# Acc_Comp_Gyro.net
KiCad netlist of a schematic drawn in EAGLE
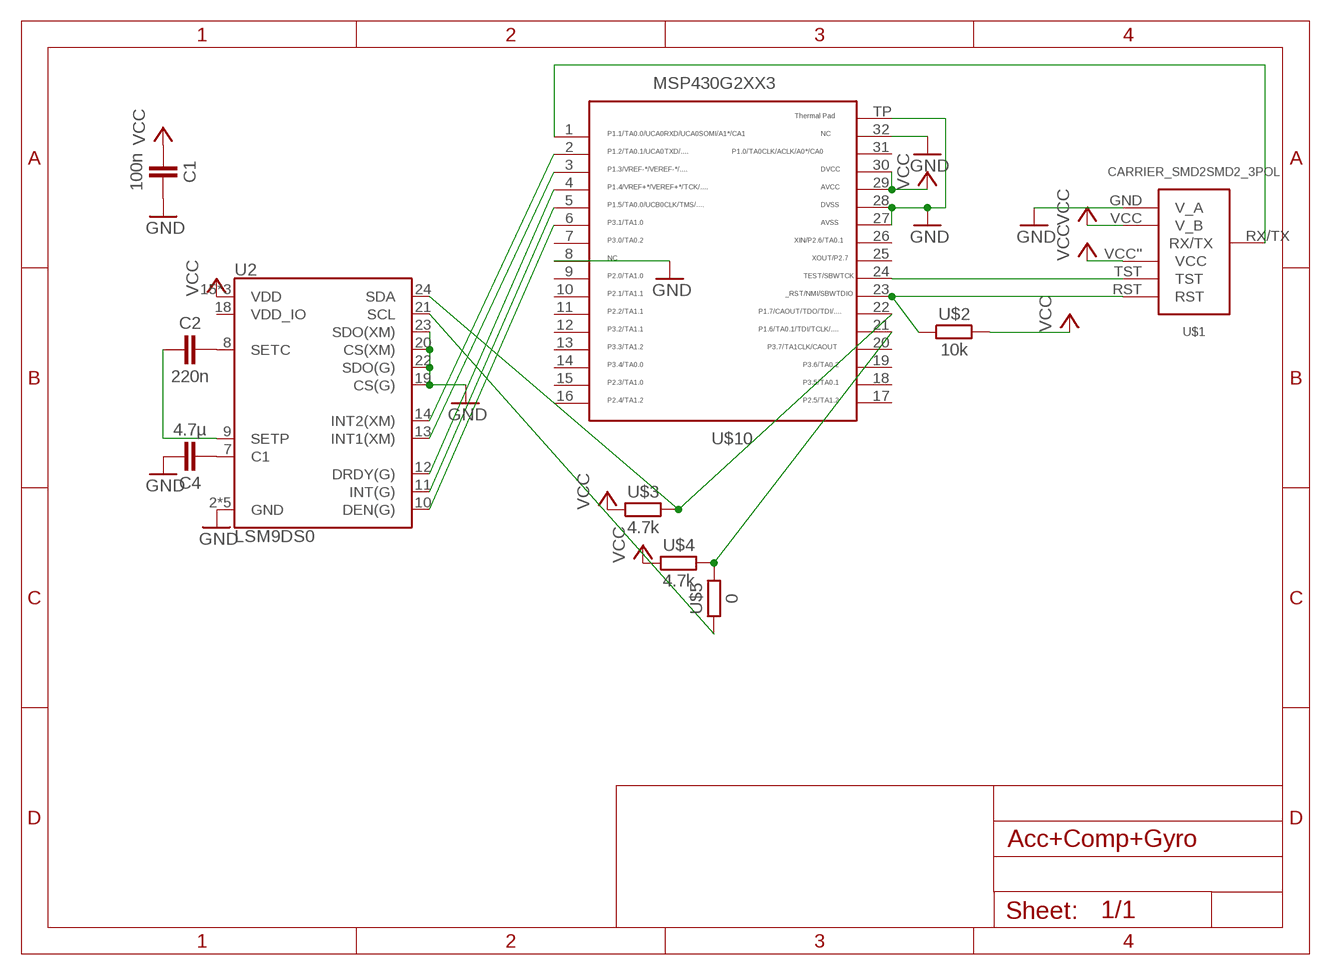
[diagram p0: schematic, sheet 1]

(export (version "E")
  (design (tool "Eeschema 10.0.6"))
  (components
    (comp (ref "C1")
      (value "100n")
      (footprint "eagle-import:603")
      (libsource (lib "eagle-import") (part "CAPACITOR"))
    )
    (comp (ref "C2")
      (value "220n")
      (footprint "eagle-import:603")
      (libsource (lib "eagle-import") (part "CAPACITOR"))
    )
    (comp (ref "C4")
      (value "4.7µ")
      (footprint "eagle-import:603")
      (libsource (lib "eagle-import") (part "CAPACITOR"))
    )
    (comp (ref "U$1")
      (value "CARRIER_SMD2SMD2_3POL")
      (footprint "eagle-import:CARRIER_SMD2_3POL")
      (libsource (lib "eagle-import") (part "CARRIER_SMD2SMD2_3POL"))
    )
    (comp (ref "U$2")
      (value "10k")
      (footprint "eagle-import:603")
      (libsource (lib "eagle-import") (part "RESISTOR0603"))
    )
    (comp (ref "U$3")
      (value "4.7k")
      (footprint "eagle-import:603")
      (libsource (lib "eagle-import") (part "RESISTOR0603"))
    )
    (comp (ref "U$4")
      (value "4.7k")
      (footprint "eagle-import:603")
      (libsource (lib "eagle-import") (part "RESISTOR0603"))
    )
    (comp (ref "U$5")
      (value "0")
      (footprint "eagle-import:603")
      (libsource (lib "eagle-import") (part "RESISTOR0603"))
    )
    (comp (ref "U$10")
      (value "MSP430G2553")
      (footprint "eagle-import:QFN32")
      (libsource (lib "eagle-import") (part "MSP430G2553"))
    )
    (comp (ref "U2")
      (value "LSM9DS0")
      (footprint "eagle-import:LGA-24")
      (libsource (lib "eagle-import") (part "LSM9DS0"))
    )
  )
  (nets
    (net (code "1") (name "GND") (class "Default")
      (node (ref "C1") (pin "2") (pinfunction "2_2") (pintype "passive"))
      (node (ref "C4") (pin "2") (pinfunction "2_2") (pintype "passive"))
      (node (ref "U$1") (pin "GND") (pinfunction "V_A_GND") (pintype "bidirectional"))
      (node (ref "U$10") (pin "27") (pinfunction "27_27") (pintype "bidirectional"))
      (node (ref "U$10") (pin "28") (pinfunction "28_28") (pintype "bidirectional"))
      (node (ref "U$10") (pin "32") (pinfunction "32_32") (pintype "bidirectional"))
      (node (ref "U$10") (pin "8") (pinfunction "8_8") (pintype "bidirectional"))
      (node (ref "U$10") (pin "TP") (pinfunction "TP_TP") (pintype "bidirectional"))
      (node (ref "U2") (pin "19") (pinfunction "CS(G)_19") (pintype "bidirectional"))
      (node (ref "U2") (pin "2") (pinfunction "GND_2") (pintype "bidirectional"))
      (node (ref "U2") (pin "20") (pinfunction "CS(XM)_20") (pintype "bidirectional"))
      (node (ref "U2") (pin "22") (pinfunction "SDO(G)_22") (pintype "bidirectional"))
      (node (ref "U2") (pin "23") (pinfunction "SDO(XM)_23") (pintype "bidirectional"))
      (node (ref "U2") (pin "3") (pinfunction "GND_3") (pintype "bidirectional"))
      (node (ref "U2") (pin "4") (pinfunction "GND_4") (pintype "bidirectional"))
      (node (ref "U2") (pin "5") (pinfunction "GND_5") (pintype "bidirectional"))
      (node (ref "U2") (pin "6") (pinfunction "GND_6") (pintype "bidirectional"))
    )
    (net (code "2") (name "Net-(U$1-PadRST)") (class "Default")
      (node (ref "U$1") (pin "RST") (pinfunction "RST_RST") (pintype "bidirectional"))
      (node (ref "U$10") (pin "23") (pinfunction "23_23") (pintype "bidirectional"))
      (node (ref "U$2") (pin "1") (pinfunction "1_1") (pintype "passive"))
    )
    (net (code "3") (name "Net-(U$1-PadRX{slash}TX)") (class "Default")
      (node (ref "U$1") (pin "RX/TX") (pinfunction "RX/TX_RX/TX") (pintype "bidirectional"))
      (node (ref "U$10") (pin "1") (pinfunction "1_1") (pintype "bidirectional"))
    )
    (net (code "4") (name "Net-(U$1-PadTST)") (class "Default")
      (node (ref "U$1") (pin "TST") (pinfunction "TST_TST") (pintype "bidirectional"))
      (node (ref "U$10") (pin "24") (pinfunction "24_24") (pintype "bidirectional"))
    )
    (net (code "5") (name "Net-(U$10-Pad21)") (class "Default")
      (node (ref "U$10") (pin "21") (pinfunction "21_21") (pintype "bidirectional"))
      (node (ref "U$4") (pin "2") (pinfunction "2_2") (pintype "passive"))
      (node (ref "U$5") (pin "2") (pinfunction "2_2") (pintype "passive"))
    )
    (net (code "6") (name "Net-(U2-C1)") (class "Default")
      (node (ref "C4") (pin "1") (pinfunction "1_1") (pintype "passive"))
      (node (ref "U2") (pin "7") (pinfunction "C1_7") (pintype "bidirectional"))
    )
    (net (code "7") (name "Net-(U2-DEN(G))") (class "Default")
      (node (ref "U$10") (pin "6") (pinfunction "6_6") (pintype "bidirectional"))
      (node (ref "U2") (pin "10") (pinfunction "DEN(G)_10") (pintype "bidirectional"))
    )
    (net (code "8") (name "Net-(U2-DRDY(G))") (class "Default")
      (node (ref "U$10") (pin "4") (pinfunction "4_4") (pintype "bidirectional"))
      (node (ref "U2") (pin "12") (pinfunction "DRDY(G)_12") (pintype "bidirectional"))
    )
    (net (code "9") (name "Net-(U2-INT(G))") (class "Default")
      (node (ref "U$10") (pin "5") (pinfunction "5_5") (pintype "bidirectional"))
      (node (ref "U2") (pin "11") (pinfunction "INT(G)_11") (pintype "bidirectional"))
    )
    (net (code "10") (name "Net-(U2-INT1(XM))") (class "Default")
      (node (ref "U$10") (pin "3") (pinfunction "3_3") (pintype "bidirectional"))
      (node (ref "U2") (pin "13") (pinfunction "INT1(XM)_13") (pintype "bidirectional"))
    )
    (net (code "11") (name "Net-(U2-INT2(XM))") (class "Default")
      (node (ref "U$10") (pin "2") (pinfunction "2_2") (pintype "bidirectional"))
      (node (ref "U2") (pin "14") (pinfunction "INT2(XM)_14") (pintype "bidirectional"))
    )
    (net (code "12") (name "Net-(U2-SCL)") (class "Default")
      (node (ref "U$5") (pin "1") (pinfunction "1_1") (pintype "passive"))
      (node (ref "U2") (pin "21") (pinfunction "SCL_21") (pintype "bidirectional"))
    )
    (net (code "13") (name "Net-(U2-SDA)") (class "Default")
      (node (ref "U$10") (pin "22") (pinfunction "22_22") (pintype "bidirectional"))
      (node (ref "U$3") (pin "2") (pinfunction "2_2") (pintype "passive"))
      (node (ref "U2") (pin "24") (pinfunction "SDA_24") (pintype "bidirectional"))
    )
    (net (code "14") (name "Net-(U2-SETC)") (class "Default")
      (node (ref "C2") (pin "2") (pinfunction "2_2") (pintype "passive"))
      (node (ref "U2") (pin "8") (pinfunction "SETC_8") (pintype "bidirectional"))
    )
    (net (code "15") (name "Net-(U2-SETP)") (class "Default")
      (node (ref "C2") (pin "1") (pinfunction "1_1") (pintype "passive"))
      (node (ref "U2") (pin "9") (pinfunction "SETP_9") (pintype "bidirectional"))
    )
    (net (code "16") (name "VCC") (class "Default")
      (node (ref "C1") (pin "1") (pinfunction "1_1") (pintype "passive"))
      (node (ref "U$1") (pin "VCC") (pinfunction "V_B_VCC") (pintype "bidirectional"))
      (node (ref "U$1") (pin "VCC''") (pinfunction "VCC_VCC''") (pintype "bidirectional"))
      (node (ref "U$10") (pin "29") (pinfunction "29_29") (pintype "bidirectional"))
      (node (ref "U$10") (pin "30") (pinfunction "30_30") (pintype "bidirectional"))
      (node (ref "U$2") (pin "2") (pinfunction "2_2") (pintype "passive"))
      (node (ref "U$3") (pin "1") (pinfunction "1_1") (pintype "passive"))
      (node (ref "U$4") (pin "1") (pinfunction "1_1") (pintype "passive"))
      (node (ref "U2") (pin "15") (pinfunction "VDD_15") (pintype "bidirectional"))
      (node (ref "U2") (pin "16") (pinfunction "VDD_16") (pintype "bidirectional"))
      (node (ref "U2") (pin "17") (pinfunction "VDD_17") (pintype "bidirectional"))
    )
    (net (code "17") (name "unconnected-(U$10-Pad7)") (class "Default")
      (node (ref "U$10") (pin "7") (pinfunction "7_7") (pintype "bidirectional"))
    )
    (net (code "18") (name "unconnected-(U$10-Pad9)") (class "Default")
      (node (ref "U$10") (pin "9") (pinfunction "9_9") (pintype "bidirectional"))
    )
    (net (code "19") (name "unconnected-(U$10-Pad10)") (class "Default")
      (node (ref "U$10") (pin "10") (pinfunction "10_10") (pintype "bidirectional"))
    )
    (net (code "20") (name "unconnected-(U$10-Pad11)") (class "Default")
      (node (ref "U$10") (pin "11") (pinfunction "11_11") (pintype "bidirectional"))
    )
    (net (code "21") (name "unconnected-(U$10-Pad12)") (class "Default")
      (node (ref "U$10") (pin "12") (pinfunction "12_12") (pintype "bidirectional"))
    )
    (net (code "22") (name "unconnected-(U$10-Pad13)") (class "Default")
      (node (ref "U$10") (pin "13") (pinfunction "13_13") (pintype "bidirectional"))
    )
    (net (code "23") (name "unconnected-(U$10-Pad14)") (class "Default")
      (node (ref "U$10") (pin "14") (pinfunction "14_14") (pintype "bidirectional"))
    )
    (net (code "24") (name "unconnected-(U$10-Pad15)") (class "Default")
      (node (ref "U$10") (pin "15") (pinfunction "15_15") (pintype "bidirectional"))
    )
    (net (code "25") (name "unconnected-(U$10-Pad16)") (class "Default")
      (node (ref "U$10") (pin "16") (pinfunction "16_16") (pintype "bidirectional"))
    )
    (net (code "26") (name "unconnected-(U$10-Pad17)") (class "Default")
      (node (ref "U$10") (pin "17") (pinfunction "17_17") (pintype "bidirectional"))
    )
    (net (code "27") (name "unconnected-(U$10-Pad18)") (class "Default")
      (node (ref "U$10") (pin "18") (pinfunction "18_18") (pintype "bidirectional"))
    )
    (net (code "28") (name "unconnected-(U$10-Pad19)") (class "Default")
      (node (ref "U$10") (pin "19") (pinfunction "19_19") (pintype "bidirectional"))
    )
    (net (code "29") (name "unconnected-(U$10-Pad20)") (class "Default")
      (node (ref "U$10") (pin "20") (pinfunction "20_20") (pintype "bidirectional"))
    )
    (net (code "30") (name "unconnected-(U$10-Pad25)") (class "Default")
      (node (ref "U$10") (pin "25") (pinfunction "25_25") (pintype "bidirectional"))
    )
    (net (code "31") (name "unconnected-(U$10-Pad26)") (class "Default")
      (node (ref "U$10") (pin "26") (pinfunction "26_26") (pintype "bidirectional"))
    )
    (net (code "32") (name "unconnected-(U$10-Pad31)") (class "Default")
      (node (ref "U$10") (pin "31") (pinfunction "31_31") (pintype "bidirectional"))
    )
    (net (code "33") (name "unconnected-(U2-VDD_IO-Pad18)") (class "Default")
      (node (ref "U2") (pin "18") (pinfunction "VDD_IO_18") (pintype "bidirectional"))
    )
  )
)
